# LM2596.net
KiCad netlist of a schematic drawn in Altium Designer
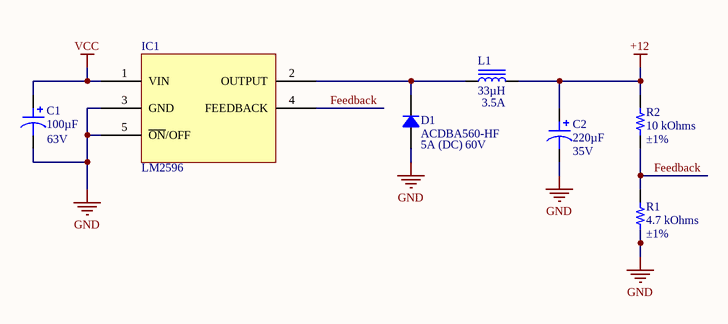
[diagram p0: LM2596.SchDoc]

(export (version "E")
  (design (tool "Eeschema 10.0.6"))
  (components
    (comp (ref "C1")
      (value "100µF")
      (footprint "CAP TH ALUM ELEC D8.00mm S3.50mm H12.50mm")
      (description "CAP ALUM 100UF 20% 63V RADIAL")
      (fields
        (field (name "PART NUMBER") "ECA-1JM101")
        (field (name "MANUFACTURER") "Panasonic Electronic Components")
        (field (name "VOLTAGE - RATED") "63V")
      )
      (libsource (lib "Celestial Altium Library - altium_library") (part "Polarised Capacitor"))
    )
    (comp (ref "C2")
      (value "220µF")
      (footprint "CAP TH ALUM ELEC D8.00mm S3.50mm H12.50mm")
      (description "CAP ALUM 220UF 20% 35V RADIAL")
      (fields
        (field (name "PART NUMBER") "ECA-1VM221")
        (field (name "MANUFACTURER") "Panasonic Electronic Components")
        (field (name "VOLTAGE - RATED") "35V")
      )
      (libsource (lib "Celestial Altium Library - altium_library") (part "Polarised Capacitor"))
    )
    (comp (ref "D1")
      (value "ACDBA560-HF")
      (footprint "DO214AC SMA")
      (description "DIODE SCHOTTKY 60V 5A DO214AC")
      (fields
        (field (name "CURRENT - AVERAGE RECTIFIED (IO)") "5A (DC)")
        (field (name "MANUFACTURER") "Comchip Technology")
        (field (name "VOLTAGE - DC REVERSE (VR) (MAX)") "60V")
      )
      (libsource (lib "Celestial Altium Library - altium_library") (part "Diode"))
    )
    (comp (ref "IC1")
      (value "LM2596")
      (footprint "D2PAK")
      (libsource (lib "BuckConverter_Library") (part "LM2596"))
    )
    (comp (ref "L1")
      (value "33µH")
      (footprint "BOURNS SRR1280")
      (description "FIXED IND 33UH 3.5A 57 MOHM SMD")
      (fields
        (field (name "PART NUMBER") "SRR1280-330M")
        (field (name "CURRENT RATING (AMPS)") "3.5A")
        (field (name "MANUFACTURER") "Bourns Inc.")
      )
      (libsource (lib "Celestial Altium Library - altium_library") (part "Inductor"))
    )
    (comp (ref "R1")
      (value "4.7 kOhms")
      (footprint "RES 0805_2012")
      (description "RES SMD 4.7K OHM 1% 1/8W 0805")
      (fields
        (field (name "PART NUMBER") "RC0805FR-074K7P")
        (field (name "MANUFACTURER") "Yageo")
        (field (name "TOLERANCE") "±1%")
      )
      (libsource (lib "Celestial Altium Library - altium_library") (part "Resistor"))
    )
    (comp (ref "R2")
      (value "10 kOhms")
      (footprint "RES 0805_2012")
      (description "RES 10K OHM 1% 1/4W 0805")
      (fields
        (field (name "PART NUMBER") "RNCP0805FTD10K0")
        (field (name "MANUFACTURER") "Stackpole Electronics Inc")
        (field (name "TOLERANCE") "±1%")
      )
      (libsource (lib "Celestial Altium Library - altium_library") (part "Resistor"))
    )
  )
  (nets
    (net (code "1") (name "+12") (class "Default")
      (node (ref "C2") (pin "1") (pinfunction "1_1") (pintype "passive"))
      (node (ref "L1") (pin "2") (pinfunction "2_2") (pintype "passive"))
      (node (ref "R2") (pin "2") (pinfunction "2_2") (pintype "passive"))
    )
    (net (code "2") (name "/Feedback") (class "Default")
      (node (ref "IC1") (pin "4") (pinfunction "FEEDBACK_4") (pintype "passive"))
      (node (ref "R1") (pin "2") (pinfunction "2_2") (pintype "passive"))
      (node (ref "R2") (pin "1") (pinfunction "1_1") (pintype "passive"))
    )
    (net (code "3") (name "GND") (class "Default")
      (node (ref "C1") (pin "2") (pinfunction "2_2") (pintype "passive"))
      (node (ref "C2") (pin "2") (pinfunction "2_2") (pintype "passive"))
      (node (ref "D1") (pin "1") (pinfunction "1_1") (pintype "passive"))
      (node (ref "IC1") (pin "3") (pinfunction "GND_3") (pintype "passive"))
      (node (ref "IC1") (pin "5") (pinfunction "~{ON}/OFF_5") (pintype "passive"))
      (node (ref "R1") (pin "1") (pinfunction "1_1") (pintype "passive"))
    )
    (net (code "4") (name "Net-(IC1-OUTPUT)") (class "Default")
      (node (ref "D1") (pin "2") (pinfunction "2_2") (pintype "passive"))
      (node (ref "IC1") (pin "2") (pinfunction "OUTPUT_2") (pintype "passive"))
      (node (ref "L1") (pin "1") (pinfunction "1_1") (pintype "passive"))
    )
    (net (code "5") (name "VCC") (class "Default")
      (node (ref "C1") (pin "1") (pinfunction "1_1") (pintype "passive"))
      (node (ref "IC1") (pin "1") (pinfunction "VIN_1") (pintype "passive"))
    )
  )
)
